# LaserPointerRemote.net
KiCad netlist of a schematic drawn in EAGLE
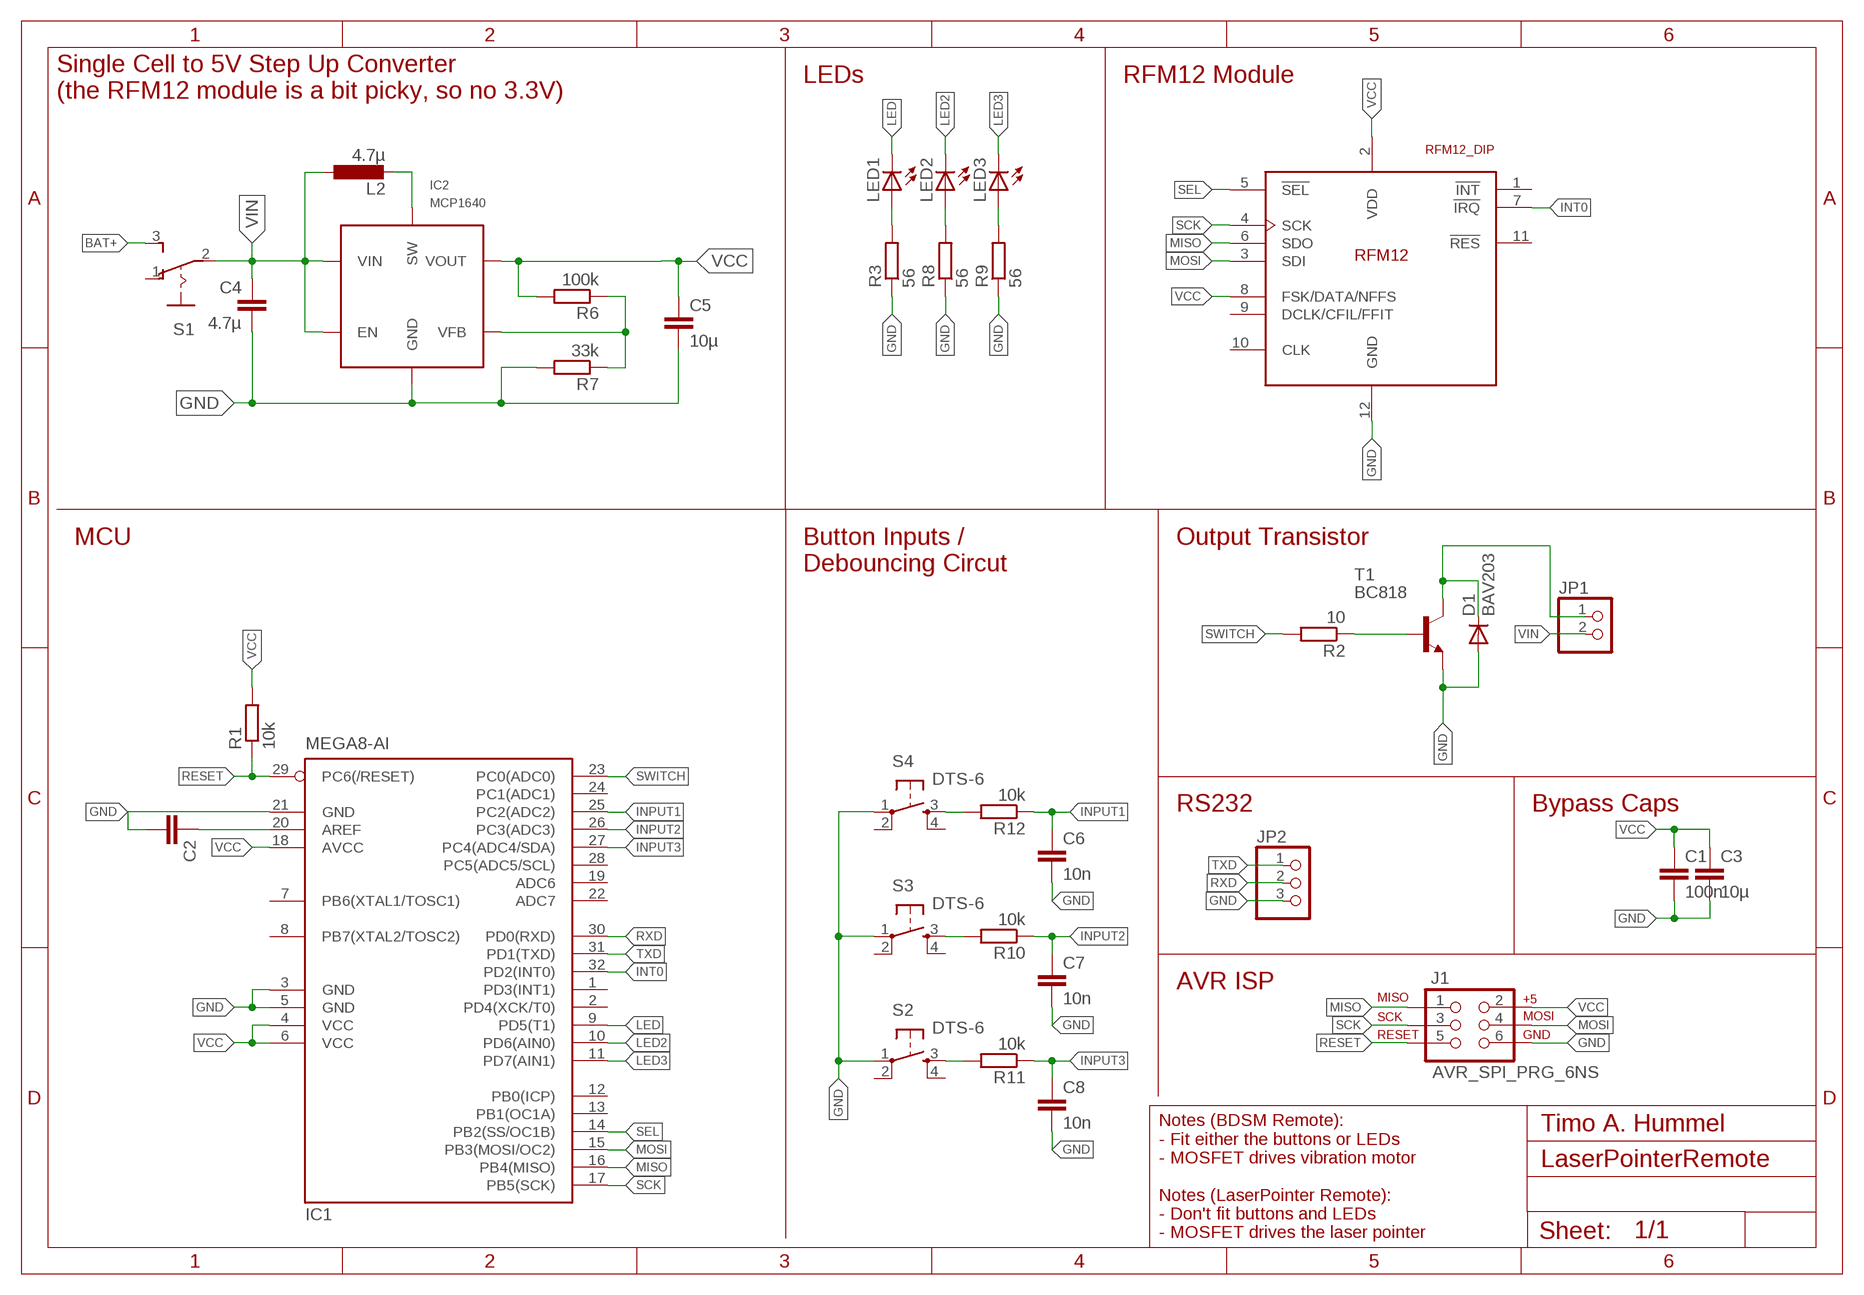
[diagram p0: schematic, sheet 1]

(export (version "E")
  (design (tool "Eeschema 10.0.6"))
  (components
    (comp (ref "C1")
      (value "100n")
      (footprint "eagle-import:C0805")
      (libsource (lib "eagle-import") (part "C-EUC0805"))
    )
    (comp (ref "C2")
      (value "C-EUC0805")
      (footprint "eagle-import:C0805")
      (libsource (lib "eagle-import") (part "C-EUC0805"))
    )
    (comp (ref "C3")
      (value "10µ")
      (footprint "eagle-import:C0805")
      (libsource (lib "eagle-import") (part "C-EUC0805"))
    )
    (comp (ref "C4")
      (value "4.7µ")
      (footprint "eagle-import:C0805")
      (libsource (lib "eagle-import") (part "C-EUC0805"))
    )
    (comp (ref "C5")
      (value "10µ")
      (footprint "eagle-import:C0805")
      (libsource (lib "eagle-import") (part "C-EUC0805"))
    )
    (comp (ref "C6")
      (value "10n")
      (footprint "eagle-import:C0805")
      (libsource (lib "eagle-import") (part "C-EUC0805"))
    )
    (comp (ref "C7")
      (value "10n")
      (footprint "eagle-import:C0805")
      (libsource (lib "eagle-import") (part "C-EUC0805"))
    )
    (comp (ref "C8")
      (value "10n")
      (footprint "eagle-import:C0805")
      (libsource (lib "eagle-import") (part "C-EUC0805"))
    )
    (comp (ref "D1")
      (value "BAV203")
      (footprint "eagle-import:SOD80C")
      (libsource (lib "eagle-import") (part "DIODE-SOD80C"))
    )
    (comp (ref "IC1")
      (value "MEGA8-AI")
      (footprint "eagle-import:TQFP32-08")
      (fields (field (name "MPN") "ATMEGA8-16AU"))
      (libsource (lib "eagle-import") (part "MEGA8-AI"))
    )
    (comp (ref "IC2")
      (value "MCP1640")
      (footprint "eagle-import:SOT23-6")
      (libsource (lib "eagle-import") (part "MCP1640"))
    )
    (comp (ref "J1")
      (value "AVR_SPI_PRG_6NS")
      (footprint "eagle-import:2X3-NS")
      (libsource (lib "eagle-import") (part "AVR_SPI_PRG_6NS"))
    )
    (comp (ref "JP1")
      (value "PINHD-1X2")
      (footprint "eagle-import:1X02")
      (libsource (lib "eagle-import") (part "PINHD-1X2"))
    )
    (comp (ref "JP2")
      (value "PINHD-1X3")
      (footprint "eagle-import:1X03")
      (libsource (lib "eagle-import") (part "PINHD-1X3"))
    )
    (comp (ref "L2")
      (value "4.7µ")
      (footprint "eagle-import:PISG")
      (libsource (lib "eagle-import") (part "L-EUPISG"))
    )
    (comp (ref "LED1")
      (value "LED3MM")
      (footprint "eagle-import:LED3MM")
      (libsource (lib "eagle-import") (part "LED3MM"))
    )
    (comp (ref "LED2")
      (value "LED3MM")
      (footprint "eagle-import:LED3MM")
      (libsource (lib "eagle-import") (part "LED3MM"))
    )
    (comp (ref "LED3")
      (value "LED3MM")
      (footprint "eagle-import:LED3MM")
      (libsource (lib "eagle-import") (part "LED3MM"))
    )
    (comp (ref "R1")
      (value "10k")
      (footprint "eagle-import:R0805")
      (libsource (lib "eagle-import") (part "R-EU_R0805"))
    )
    (comp (ref "R2")
      (value "10")
      (footprint "eagle-import:R0805")
      (libsource (lib "eagle-import") (part "R-EU_R0805"))
    )
    (comp (ref "R3")
      (value "56")
      (footprint "eagle-import:R0805")
      (libsource (lib "eagle-import") (part "R-EU_R0805"))
    )
    (comp (ref "R6")
      (value "100k")
      (footprint "eagle-import:R0805")
      (libsource (lib "eagle-import") (part "R-EU_R0805"))
    )
    (comp (ref "R7")
      (value "33k")
      (footprint "eagle-import:R0805")
      (libsource (lib "eagle-import") (part "R-EU_R0805"))
    )
    (comp (ref "R8")
      (value "56")
      (footprint "eagle-import:R0805")
      (libsource (lib "eagle-import") (part "R-EU_R0805"))
    )
    (comp (ref "R9")
      (value "56")
      (footprint "eagle-import:R0805")
      (libsource (lib "eagle-import") (part "R-EU_R0805"))
    )
    (comp (ref "R10")
      (value "10k")
      (footprint "eagle-import:R0805")
      (libsource (lib "eagle-import") (part "R-EU_R0805"))
    )
    (comp (ref "R11")
      (value "10k")
      (footprint "eagle-import:R0805")
      (libsource (lib "eagle-import") (part "R-EU_R0805"))
    )
    (comp (ref "R12")
      (value "10k")
      (footprint "eagle-import:R0805")
      (libsource (lib "eagle-import") (part "R-EU_R0805"))
    )
    (comp (ref "S1")
      (value "SS12")
      (footprint "eagle-import:NKKSS-12")
      (libsource (lib "eagle-import") (part "SS12"))
    )
    (comp (ref "S2")
      (value "DTS-6")
      (footprint "eagle-import:DTS-6")
      (libsource (lib "eagle-import") (part "DTS-6"))
    )
    (comp (ref "S3")
      (value "DTS-6")
      (footprint "eagle-import:DTS-6")
      (libsource (lib "eagle-import") (part "DTS-6"))
    )
    (comp (ref "S4")
      (value "DTS-6")
      (footprint "eagle-import:DTS-6")
      (libsource (lib "eagle-import") (part "DTS-6"))
    )
    (comp (ref "T1")
      (value "BC818")
      (footprint "eagle-import:SOT23-BEC")
      (libsource (lib "eagle-import") (part "-NPN-SOT23-BECBC818-16"))
    )
    (comp (ref "U$1")
      (value "RFM12_DIP")
      (footprint "eagle-import:DIL-2MM-2X06")
      (libsource (lib "eagle-import") (part "RFM12_DIP"))
    )
  )
  (nets
    (net (code "1") (name "BAT+") (class "Default")
      (node (ref "S1") (pin "3") (pinfunction "S_3") (pintype "passive"))
    )
    (net (code "2") (name "GND") (class "Default")
      (node (ref "C1") (pin "2") (pinfunction "2_2") (pintype "passive"))
      (node (ref "C2") (pin "2") (pinfunction "2_2") (pintype "passive"))
      (node (ref "C3") (pin "2") (pinfunction "2_2") (pintype "passive"))
      (node (ref "C4") (pin "2") (pinfunction "2_2") (pintype "passive"))
      (node (ref "C5") (pin "2") (pinfunction "2_2") (pintype "passive"))
      (node (ref "C6") (pin "2") (pinfunction "2_2") (pintype "passive"))
      (node (ref "C7") (pin "2") (pinfunction "2_2") (pintype "passive"))
      (node (ref "C8") (pin "2") (pinfunction "2_2") (pintype "passive"))
      (node (ref "D1") (pin "A") (pinfunction "A_A") (pintype "passive"))
      (node (ref "IC1") (pin "21") (pinfunction "GND_21") (pintype "power_in"))
      (node (ref "IC1") (pin "3") (pinfunction "GND_3") (pintype "power_in"))
      (node (ref "IC1") (pin "5") (pinfunction "GND_5") (pintype "power_in"))
      (node (ref "IC2") (pin "2") (pinfunction "GND_2") (pintype "power_in"))
      (node (ref "J1") (pin "6") (pinfunction "6_6") (pintype "passive"))
      (node (ref "JP2") (pin "3") (pinfunction "3_3") (pintype "passive"))
      (node (ref "R3") (pin "1") (pinfunction "1_1") (pintype "passive"))
      (node (ref "R7") (pin "2") (pinfunction "2_2") (pintype "passive"))
      (node (ref "R8") (pin "1") (pinfunction "1_1") (pintype "passive"))
      (node (ref "R9") (pin "1") (pinfunction "1_1") (pintype "passive"))
      (node (ref "S2") (pin "1") (pinfunction "1_1") (pintype "passive"))
      (node (ref "S3") (pin "1") (pinfunction "1_1") (pintype "passive"))
      (node (ref "S4") (pin "1") (pinfunction "1_1") (pintype "passive"))
      (node (ref "T1") (pin "E") (pinfunction "E_E") (pintype "passive"))
      (node (ref "U$1") (pin "12") (pinfunction "GND_12") (pintype "passive"))
    )
    (net (code "3") (name "INPUT1") (class "Default")
      (node (ref "C6") (pin "1") (pinfunction "1_1") (pintype "passive"))
      (node (ref "IC1") (pin "25") (pinfunction "PC2(ADC2)_25") (pintype "bidirectional"))
      (node (ref "R12") (pin "1") (pinfunction "1_1") (pintype "passive"))
    )
    (net (code "4") (name "INPUT2") (class "Default")
      (node (ref "C7") (pin "1") (pinfunction "1_1") (pintype "passive"))
      (node (ref "IC1") (pin "26") (pinfunction "PC3(ADC3)_26") (pintype "bidirectional"))
      (node (ref "R10") (pin "1") (pinfunction "1_1") (pintype "passive"))
    )
    (net (code "5") (name "INPUT3") (class "Default")
      (node (ref "C8") (pin "1") (pinfunction "1_1") (pintype "passive"))
      (node (ref "IC1") (pin "27") (pinfunction "PC4(ADC4/SDA)_27") (pintype "bidirectional"))
      (node (ref "R11") (pin "1") (pinfunction "1_1") (pintype "passive"))
    )
    (net (code "6") (name "INT0") (class "Default")
      (node (ref "IC1") (pin "32") (pinfunction "PD2(INT0)_32") (pintype "bidirectional"))
      (node (ref "U$1") (pin "7") (pinfunction "~{IRQ}_7") (pintype "output"))
    )
    (net (code "7") (name "LED") (class "Default")
      (node (ref "IC1") (pin "9") (pinfunction "PD5(T1)_9") (pintype "bidirectional"))
      (node (ref "LED1") (pin "K") (pinfunction "C_K") (pintype "passive"))
    )
    (net (code "8") (name "LED2") (class "Default")
      (node (ref "IC1") (pin "10") (pinfunction "PD6(AIN0)_10") (pintype "bidirectional"))
      (node (ref "LED2") (pin "K") (pinfunction "C_K") (pintype "passive"))
    )
    (net (code "9") (name "LED3") (class "Default")
      (node (ref "IC1") (pin "11") (pinfunction "PD7(AIN1)_11") (pintype "bidirectional"))
      (node (ref "LED3") (pin "K") (pinfunction "C_K") (pintype "passive"))
    )
    (net (code "10") (name "MISO") (class "Default")
      (node (ref "IC1") (pin "16") (pinfunction "PB4(MISO)_16") (pintype "bidirectional"))
      (node (ref "J1") (pin "1") (pinfunction "1_1") (pintype "passive"))
      (node (ref "U$1") (pin "6") (pinfunction "SDO_6") (pintype "output"))
    )
    (net (code "11") (name "MOSI") (class "Default")
      (node (ref "IC1") (pin "15") (pinfunction "PB3(MOSI/OC2)_15") (pintype "bidirectional"))
      (node (ref "J1") (pin "4") (pinfunction "4_4") (pintype "passive"))
      (node (ref "U$1") (pin "3") (pinfunction "SDI_3") (pintype "input"))
    )
    (net (code "12") (name "Net-(D1-PadC)") (class "Default")
      (node (ref "D1") (pin "C") (pinfunction "C_C") (pintype "passive"))
      (node (ref "JP1") (pin "1") (pinfunction "1_1") (pintype "passive"))
      (node (ref "T1") (pin "C") (pinfunction "C_C") (pintype "passive"))
    )
    (net (code "13") (name "Net-(IC1-AREF)") (class "Default")
      (node (ref "C2") (pin "1") (pinfunction "1_1") (pintype "passive"))
      (node (ref "IC1") (pin "20") (pinfunction "AREF_20") (pintype "passive"))
    )
    (net (code "14") (name "Net-(IC2-SW)") (class "Default")
      (node (ref "IC2") (pin "1") (pinfunction "SW_1") (pintype "passive"))
      (node (ref "L2") (pin "2") (pinfunction "2_2") (pintype "passive"))
    )
    (net (code "15") (name "Net-(IC2-VFB)") (class "Default")
      (node (ref "IC2") (pin "4") (pinfunction "VFB_4") (pintype "input"))
      (node (ref "R6") (pin "1") (pinfunction "1_1") (pintype "passive"))
      (node (ref "R7") (pin "1") (pinfunction "1_1") (pintype "passive"))
    )
    (net (code "16") (name "Net-(LED1-PadA)") (class "Default")
      (node (ref "LED1") (pin "A") (pinfunction "A_A") (pintype "passive"))
      (node (ref "R3") (pin "2") (pinfunction "2_2") (pintype "passive"))
    )
    (net (code "17") (name "Net-(LED2-PadA)") (class "Default")
      (node (ref "LED2") (pin "A") (pinfunction "A_A") (pintype "passive"))
      (node (ref "R8") (pin "2") (pinfunction "2_2") (pintype "passive"))
    )
    (net (code "18") (name "Net-(LED3-PadA)") (class "Default")
      (node (ref "LED3") (pin "A") (pinfunction "A_A") (pintype "passive"))
      (node (ref "R9") (pin "2") (pinfunction "2_2") (pintype "passive"))
    )
    (net (code "19") (name "Net-(R2-Pad1)") (class "Default")
      (node (ref "R2") (pin "1") (pinfunction "1_1") (pintype "passive"))
      (node (ref "T1") (pin "B") (pinfunction "B_B") (pintype "passive"))
    )
    (net (code "20") (name "Net-(R10-Pad2)") (class "Default")
      (node (ref "R10") (pin "2") (pinfunction "2_2") (pintype "passive"))
      (node (ref "S3") (pin "3") (pinfunction "3_3") (pintype "passive"))
    )
    (net (code "21") (name "Net-(R11-Pad2)") (class "Default")
      (node (ref "R11") (pin "2") (pinfunction "2_2") (pintype "passive"))
      (node (ref "S2") (pin "3") (pinfunction "3_3") (pintype "passive"))
    )
    (net (code "22") (name "Net-(R12-Pad2)") (class "Default")
      (node (ref "R12") (pin "2") (pinfunction "2_2") (pintype "passive"))
      (node (ref "S4") (pin "3") (pinfunction "3_3") (pintype "passive"))
    )
    (net (code "23") (name "RESET") (class "Default")
      (node (ref "IC1") (pin "29") (pinfunction "PC6(/RESET)_29") (pintype "bidirectional"))
      (node (ref "J1") (pin "5") (pinfunction "5_5") (pintype "passive"))
      (node (ref "R1") (pin "1") (pinfunction "1_1") (pintype "passive"))
    )
    (net (code "24") (name "RXD") (class "Default")
      (node (ref "IC1") (pin "30") (pinfunction "PD0(RXD)_30") (pintype "bidirectional"))
      (node (ref "JP2") (pin "2") (pinfunction "2_2") (pintype "passive"))
    )
    (net (code "25") (name "SCK") (class "Default")
      (node (ref "IC1") (pin "17") (pinfunction "PB5(SCK)_17") (pintype "bidirectional"))
      (node (ref "J1") (pin "3") (pinfunction "3_3") (pintype "passive"))
      (node (ref "U$1") (pin "4") (pinfunction "SCK_4") (pintype "input"))
    )
    (net (code "26") (name "SEL") (class "Default")
      (node (ref "IC1") (pin "14") (pinfunction "PB2(SS/OC1B)_14") (pintype "bidirectional"))
      (node (ref "U$1") (pin "5") (pinfunction "~{SEL}_5") (pintype "input"))
    )
    (net (code "27") (name "SWITCH") (class "Default")
      (node (ref "IC1") (pin "23") (pinfunction "PC0(ADC0)_23") (pintype "bidirectional"))
      (node (ref "R2") (pin "2") (pinfunction "2_2") (pintype "passive"))
    )
    (net (code "28") (name "TXD") (class "Default")
      (node (ref "IC1") (pin "31") (pinfunction "PD1(TXD)_31") (pintype "bidirectional"))
      (node (ref "JP2") (pin "1") (pinfunction "1_1") (pintype "passive"))
    )
    (net (code "29") (name "VCC") (class "Default")
      (node (ref "C1") (pin "1") (pinfunction "1_1") (pintype "passive"))
      (node (ref "C3") (pin "1") (pinfunction "1_1") (pintype "passive"))
      (node (ref "C5") (pin "1") (pinfunction "1_1") (pintype "passive"))
      (node (ref "IC1") (pin "18") (pinfunction "AVCC_18") (pintype "power_in"))
      (node (ref "IC1") (pin "4") (pinfunction "VCC_4") (pintype "power_in"))
      (node (ref "IC1") (pin "6") (pinfunction "VCC_6") (pintype "power_in"))
      (node (ref "IC2") (pin "5") (pinfunction "VOUT_5") (pintype "power_in"))
      (node (ref "J1") (pin "2") (pinfunction "2_2") (pintype "passive"))
      (node (ref "R1") (pin "2") (pinfunction "2_2") (pintype "passive"))
      (node (ref "R6") (pin "2") (pinfunction "2_2") (pintype "passive"))
      (node (ref "U$1") (pin "2") (pinfunction "VDD_2") (pintype "power_in"))
      (node (ref "U$1") (pin "8") (pinfunction "FSK/DATA/NFFS_8") (pintype "bidirectional"))
    )
    (net (code "30") (name "VIN") (class "Default")
      (node (ref "C4") (pin "1") (pinfunction "1_1") (pintype "passive"))
      (node (ref "IC2") (pin "3") (pinfunction "EN_3") (pintype "input"))
      (node (ref "IC2") (pin "6") (pinfunction "VIN_6") (pintype "input"))
      (node (ref "JP1") (pin "2") (pinfunction "2_2") (pintype "passive"))
      (node (ref "L2") (pin "1") (pinfunction "1_1") (pintype "passive"))
      (node (ref "S1") (pin "2") (pinfunction "P_2") (pintype "passive"))
    )
    (net (code "31") (name "unconnected-(IC1-ADC6-Pad19)") (class "Default")
      (node (ref "IC1") (pin "19") (pinfunction "ADC6_19") (pintype "bidirectional"))
    )
    (net (code "32") (name "unconnected-(IC1-ADC7-Pad22)") (class "Default")
      (node (ref "IC1") (pin "22") (pinfunction "ADC7_22") (pintype "bidirectional"))
    )
    (net (code "33") (name "unconnected-(IC1-PB0(ICP)-Pad12)") (class "Default")
      (node (ref "IC1") (pin "12") (pinfunction "PB0(ICP)_12") (pintype "bidirectional"))
    )
    (net (code "34") (name "unconnected-(IC1-PB1(OC1A)-Pad13)") (class "Default")
      (node (ref "IC1") (pin "13") (pinfunction "PB1(OC1A)_13") (pintype "bidirectional"))
    )
    (net (code "35") (name "unconnected-(IC1-PB6(XTAL1{slash}TOSC1)-Pad7)") (class "Default")
      (node (ref "IC1") (pin "7") (pinfunction "PB6(XTAL1/TOSC1)_7") (pintype "bidirectional"))
    )
    (net (code "36") (name "unconnected-(IC1-PB7(XTAL2{slash}TOSC2)-Pad8)") (class "Default")
      (node (ref "IC1") (pin "8") (pinfunction "PB7(XTAL2/TOSC2)_8") (pintype "bidirectional"))
    )
    (net (code "37") (name "unconnected-(IC1-PC1(ADC1)-Pad24)") (class "Default")
      (node (ref "IC1") (pin "24") (pinfunction "PC1(ADC1)_24") (pintype "bidirectional"))
    )
    (net (code "38") (name "unconnected-(IC1-PC5(ADC5{slash}SCL)-Pad28)") (class "Default")
      (node (ref "IC1") (pin "28") (pinfunction "PC5(ADC5/SCL)_28") (pintype "bidirectional"))
    )
    (net (code "39") (name "unconnected-(IC1-PD3(INT1)-Pad1)") (class "Default")
      (node (ref "IC1") (pin "1") (pinfunction "PD3(INT1)_1") (pintype "bidirectional"))
    )
    (net (code "40") (name "unconnected-(IC1-PD4(XCK{slash}T0)-Pad2)") (class "Default")
      (node (ref "IC1") (pin "2") (pinfunction "PD4(XCK/T0)_2") (pintype "bidirectional"))
    )
    (net (code "41") (name "unconnected-(S1-O-Pad1)") (class "Default")
      (node (ref "S1") (pin "1") (pinfunction "O_1") (pintype "passive"))
    )
    (net (code "42") (name "unconnected-(S2-Pad2)") (class "Default")
      (node (ref "S2") (pin "2") (pinfunction "2_2") (pintype "passive"))
    )
    (net (code "43") (name "unconnected-(S2-Pad4)") (class "Default")
      (node (ref "S2") (pin "4") (pinfunction "4_4") (pintype "passive"))
    )
    (net (code "44") (name "unconnected-(S3-Pad2)") (class "Default")
      (node (ref "S3") (pin "2") (pinfunction "2_2") (pintype "passive"))
    )
    (net (code "45") (name "unconnected-(S3-Pad4)") (class "Default")
      (node (ref "S3") (pin "4") (pinfunction "4_4") (pintype "passive"))
    )
    (net (code "46") (name "unconnected-(S4-Pad2)") (class "Default")
      (node (ref "S4") (pin "2") (pinfunction "2_2") (pintype "passive"))
    )
    (net (code "47") (name "unconnected-(S4-Pad4)") (class "Default")
      (node (ref "S4") (pin "4") (pinfunction "4_4") (pintype "passive"))
    )
    (net (code "48") (name "unconnected-(U$1-CLK-Pad10)") (class "Default")
      (node (ref "U$1") (pin "10") (pinfunction "CLK_10") (pintype "output"))
    )
    (net (code "49") (name "unconnected-(U$1-DCLK{slash}CFIL{slash}FFIT-Pad9)") (class "Default")
      (node (ref "U$1") (pin "9") (pinfunction "DCLK/CFIL/FFIT_9") (pintype "bidirectional"))
    )
    (net (code "50") (name "unconnected-(U$1-~{INT}-Pad1)") (class "Default")
      (node (ref "U$1") (pin "1") (pinfunction "~{INT}_1") (pintype "bidirectional"))
    )
    (net (code "51") (name "unconnected-(U$1-~{RES}-Pad11)") (class "Default")
      (node (ref "U$1") (pin "11") (pinfunction "~{RES}_11") (pintype "bidirectional"))
    )
  )
)
